# xmas_v4.net
KiCad netlist of a schematic drawn in EAGLE
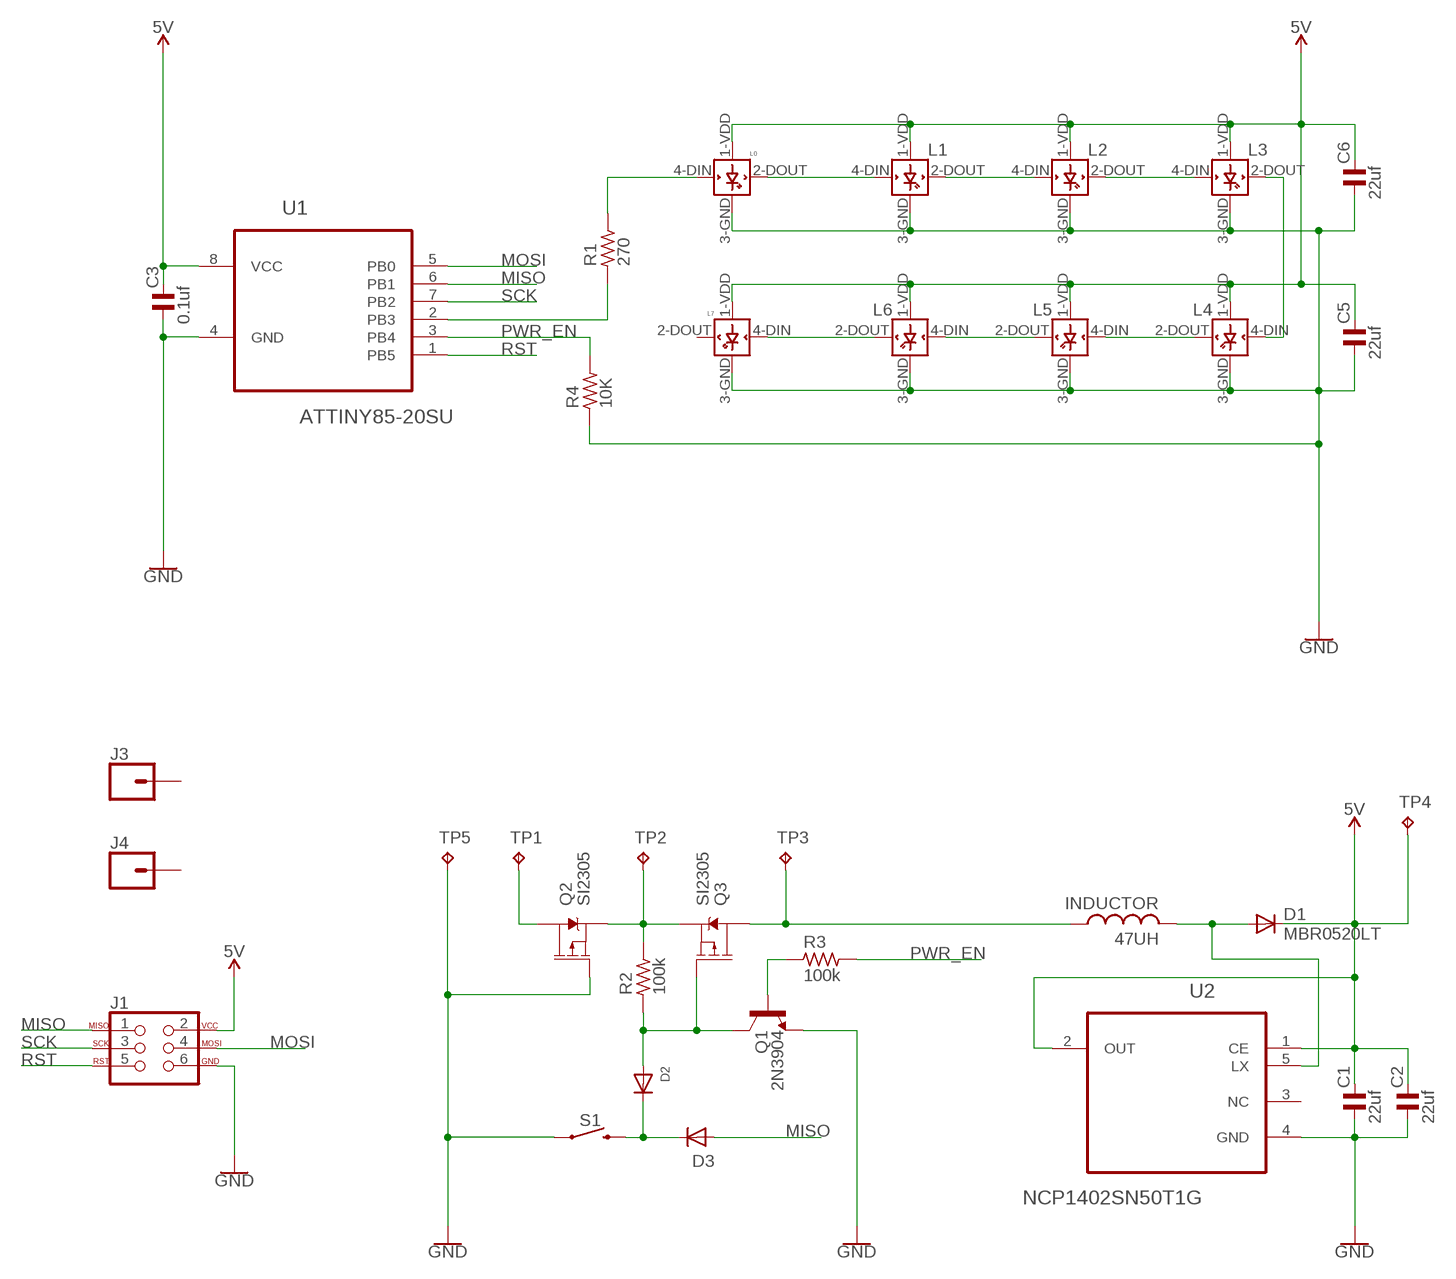
[diagram p0: schematic, sheet 1]

(export (version "E")
  (design (tool "Eeschema 10.0.6"))
  (components
    (comp (ref "47UH")
      (value "INDUCTOR")
      (footprint "eagle-import:CD32")
      (libsource (lib "eagle-import") (part "INDUCTOR"))
    )
    (comp (ref "C1")
      (value "22uf")
      (footprint "eagle-import:C0805MP")
      (libsource (lib "eagle-import") (part "C_0805MP"))
    )
    (comp (ref "C2")
      (value "22uf")
      (footprint "eagle-import:C0805MP")
      (libsource (lib "eagle-import") (part "C_0805MP"))
    )
    (comp (ref "C3")
      (value "0.1uf")
      (footprint "eagle-import:C0603MP")
      (libsource (lib "eagle-import") (part "C_0603MP"))
    )
    (comp (ref "C5")
      (value "22uf")
      (footprint "eagle-import:C0805MP")
      (libsource (lib "eagle-import") (part "C_0805MP"))
    )
    (comp (ref "C6")
      (value "22uf")
      (footprint "eagle-import:C0805MP")
      (libsource (lib "eagle-import") (part "C_0805MP"))
    )
    (comp (ref "D1")
      (value "MBR0520LT")
      (footprint "eagle-import:SOD123")
      (libsource (lib "eagle-import") (part "MBR0520LT"))
    )
    (comp (ref "D2")
      (value "DIODESOD-123")
      (footprint "eagle-import:SOD-123")
      (libsource (lib "eagle-import") (part "DIODESOD-123"))
    )
    (comp (ref "D3")
      (value "DIODESOD-123")
      (footprint "eagle-import:SOD-123")
      (libsource (lib "eagle-import") (part "DIODESOD-123"))
    )
    (comp (ref "J1")
      (value "AVR_SPI_PROG_3X2TESTPOINTS")
      (footprint "eagle-import:2X3_TEST_POINTS")
      (libsource (lib "eagle-import") (part "AVR_SPI_PROG_3X2TESTPOINTS"))
    )
    (comp (ref "J3")
      (value "CONN_01PTH_NO_SILK_KIT")
      (footprint "eagle-import:1X01NS_KIT")
      (libsource (lib "eagle-import") (part "CONN_01PTH_NO_SILK_KIT"))
    )
    (comp (ref "J4")
      (value "CONN_01PTH_NO_SILK_KIT")
      (footprint "eagle-import:1X01NS_KIT")
      (libsource (lib "eagle-import") (part "CONN_01PTH_NO_SILK_KIT"))
    )
    (comp (ref "L0")
      (value "WS2812B")
      (footprint "eagle-import:WS2812B")
      (libsource (lib "eagle-import") (part "WS2812B"))
    )
    (comp (ref "L1")
      (value "WS2812B")
      (footprint "eagle-import:WS2812B")
      (libsource (lib "eagle-import") (part "WS2812B"))
    )
    (comp (ref "L2")
      (value "WS2812B")
      (footprint "eagle-import:WS2812B")
      (libsource (lib "eagle-import") (part "WS2812B"))
    )
    (comp (ref "L3")
      (value "WS2812B")
      (footprint "eagle-import:WS2812B")
      (libsource (lib "eagle-import") (part "WS2812B"))
    )
    (comp (ref "L4")
      (value "WS2812B")
      (footprint "eagle-import:WS2812B")
      (libsource (lib "eagle-import") (part "WS2812B"))
    )
    (comp (ref "L5")
      (value "WS2812B")
      (footprint "eagle-import:WS2812B")
      (libsource (lib "eagle-import") (part "WS2812B"))
    )
    (comp (ref "L6")
      (value "WS2812B")
      (footprint "eagle-import:WS2812B")
      (libsource (lib "eagle-import") (part "WS2812B"))
    )
    (comp (ref "L7")
      (value "WS2812B")
      (footprint "eagle-import:WS2812B")
      (libsource (lib "eagle-import") (part "WS2812B"))
    )
    (comp (ref "Q1")
      (value "2N3904")
      (footprint "eagle-import:SOT23-3")
      (libsource (lib "eagle-import") (part "TRANS_NPN-MMBT2222AL"))
    )
    (comp (ref "Q2")
      (value "SI2305")
      (footprint "eagle-import:SOT23-3")
      (libsource (lib "eagle-import") (part "MOSFET_PCH-SI2309DS"))
    )
    (comp (ref "Q3")
      (value "SI2305")
      (footprint "eagle-import:SOT23-3")
      (libsource (lib "eagle-import") (part "MOSFET_PCH-SI2309DS"))
    )
    (comp (ref "R1")
      (value "270")
      (footprint "eagle-import:R0603MP")
      (libsource (lib "eagle-import") (part "R_0603MP"))
    )
    (comp (ref "R2")
      (value "100k")
      (footprint "eagle-import:R0603MP")
      (libsource (lib "eagle-import") (part "R_0603MP"))
    )
    (comp (ref "R3")
      (value "100k")
      (footprint "eagle-import:R0603MP")
      (libsource (lib "eagle-import") (part "R_0603MP"))
    )
    (comp (ref "R4")
      (value "10K")
      (footprint "eagle-import:R0805MP")
      (libsource (lib "eagle-import") (part "R_0805MP"))
    )
    (comp (ref "S1")
      (value "MOMENTARY-SWITCH-SPST-SMD-6.2MM-TALL")
      (footprint "eagle-import:TACTILE_SWITCH_SMD_6.2MM_TALL")
      (libsource (lib "eagle-import") (part "MOMENTARY-SWITCH-SPST-SMD-6.2MM-TALL"))
    )
    (comp (ref "TP1")
      (value "TPB1,27")
      (footprint "eagle-import:B1,27")
      (libsource (lib "eagle-import") (part "TPB1,27"))
    )
    (comp (ref "TP2")
      (value "TPB1,27")
      (footprint "eagle-import:B1,27")
      (libsource (lib "eagle-import") (part "TPB1,27"))
    )
    (comp (ref "TP3")
      (value "TPB1,27")
      (footprint "eagle-import:B1,27")
      (libsource (lib "eagle-import") (part "TPB1,27"))
    )
    (comp (ref "TP4")
      (value "TPB1,27")
      (footprint "eagle-import:B1,27")
      (libsource (lib "eagle-import") (part "TPB1,27"))
    )
    (comp (ref "TP5")
      (value "TPB1,27")
      (footprint "eagle-import:B1,27")
      (libsource (lib "eagle-import") (part "TPB1,27"))
    )
    (comp (ref "U1")
      (value "ATTINY85-20SU")
      (footprint "eagle-import:SOIC127P798X216-8N")
      (libsource (lib "eagle-import") (part "ATTINY85-20SU"))
    )
    (comp (ref "U2")
      (value "NCP1402SN50T1G")
      (footprint "eagle-import:SOT95P275X110-5N")
      (libsource (lib "eagle-import") (part "NCP1402SN50T1G"))
    )
  )
  (nets
    (net (code "1") (name "/MISO") (class "Default")
      (node (ref "D3") (pin "A") (pinfunction "A_A") (pintype "passive"))
      (node (ref "J1") (pin "1") (pinfunction "1_1") (pintype "passive"))
      (node (ref "U1") (pin "6") (pinfunction "PB1_6") (pintype "bidirectional"))
    )
    (net (code "2") (name "/MOSI") (class "Default")
      (node (ref "J1") (pin "4") (pinfunction "4_4") (pintype "passive"))
      (node (ref "U1") (pin "5") (pinfunction "PB0_5") (pintype "bidirectional"))
    )
    (net (code "3") (name "/PWR_EN") (class "Default")
      (node (ref "R3") (pin "2") (pinfunction "2_2") (pintype "passive"))
      (node (ref "R4") (pin "2") (pinfunction "2_2") (pintype "passive"))
      (node (ref "U1") (pin "3") (pinfunction "PB4_3") (pintype "bidirectional"))
    )
    (net (code "4") (name "/RST") (class "Default")
      (node (ref "J1") (pin "5") (pinfunction "5_5") (pintype "passive"))
      (node (ref "U1") (pin "1") (pinfunction "PB5_1") (pintype "bidirectional"))
    )
    (net (code "5") (name "/SCK") (class "Default")
      (node (ref "J1") (pin "3") (pinfunction "3_3") (pintype "passive"))
      (node (ref "U1") (pin "7") (pinfunction "PB2_7") (pintype "bidirectional"))
    )
    (net (code "6") (name "5V") (class "Default")
      (node (ref "C1") (pin "2") (pinfunction "2_2") (pintype "passive"))
      (node (ref "C2") (pin "2") (pinfunction "2_2") (pintype "passive"))
      (node (ref "C3") (pin "2") (pinfunction "2_2") (pintype "passive"))
      (node (ref "C5") (pin "2") (pinfunction "2_2") (pintype "passive"))
      (node (ref "C6") (pin "2") (pinfunction "2_2") (pintype "passive"))
      (node (ref "D1") (pin "C") (pinfunction "C_C") (pintype "passive"))
      (node (ref "J1") (pin "2") (pinfunction "2_2") (pintype "passive"))
      (node (ref "L0") (pin "1-VDD") (pinfunction "VDD_1-VDD") (pintype "bidirectional"))
      (node (ref "L1") (pin "1-VDD") (pinfunction "VDD_1-VDD") (pintype "bidirectional"))
      (node (ref "L2") (pin "1-VDD") (pinfunction "VDD_1-VDD") (pintype "bidirectional"))
      (node (ref "L3") (pin "1-VDD") (pinfunction "VDD_1-VDD") (pintype "bidirectional"))
      (node (ref "L4") (pin "1-VDD") (pinfunction "VDD_1-VDD") (pintype "bidirectional"))
      (node (ref "L5") (pin "1-VDD") (pinfunction "VDD_1-VDD") (pintype "bidirectional"))
      (node (ref "L6") (pin "1-VDD") (pinfunction "VDD_1-VDD") (pintype "bidirectional"))
      (node (ref "L7") (pin "1-VDD") (pinfunction "VDD_1-VDD") (pintype "bidirectional"))
      (node (ref "TP4") (pin "TP") (pinfunction "TP_TP") (pintype "input"))
      (node (ref "U1") (pin "8") (pinfunction "VCC_8") (pintype "power_in"))
      (node (ref "U2") (pin "1") (pinfunction "CE_1") (pintype "input"))
      (node (ref "U2") (pin "2") (pinfunction "OUT_2") (pintype "output"))
    )
    (net (code "7") (name "GND") (class "Default")
      (node (ref "C1") (pin "1") (pinfunction "1_1") (pintype "passive"))
      (node (ref "C2") (pin "1") (pinfunction "1_1") (pintype "passive"))
      (node (ref "C3") (pin "1") (pinfunction "1_1") (pintype "passive"))
      (node (ref "C5") (pin "1") (pinfunction "1_1") (pintype "passive"))
      (node (ref "C6") (pin "1") (pinfunction "1_1") (pintype "passive"))
      (node (ref "J1") (pin "6") (pinfunction "6_6") (pintype "passive"))
      (node (ref "L0") (pin "3-GND") (pinfunction "GND_3-GND") (pintype "bidirectional"))
      (node (ref "L1") (pin "3-GND") (pinfunction "GND_3-GND") (pintype "bidirectional"))
      (node (ref "L2") (pin "3-GND") (pinfunction "GND_3-GND") (pintype "bidirectional"))
      (node (ref "L3") (pin "3-GND") (pinfunction "GND_3-GND") (pintype "bidirectional"))
      (node (ref "L4") (pin "3-GND") (pinfunction "GND_3-GND") (pintype "bidirectional"))
      (node (ref "L5") (pin "3-GND") (pinfunction "GND_3-GND") (pintype "bidirectional"))
      (node (ref "L6") (pin "3-GND") (pinfunction "GND_3-GND") (pintype "bidirectional"))
      (node (ref "L7") (pin "3-GND") (pinfunction "GND_3-GND") (pintype "bidirectional"))
      (node (ref "Q1") (pin "2") (pinfunction "E_2") (pintype "passive"))
      (node (ref "Q2") (pin "1") (pinfunction "G_1") (pintype "bidirectional"))
      (node (ref "R4") (pin "1") (pinfunction "1_1") (pintype "passive"))
      (node (ref "S1") (pin "A2") (pinfunction "1_A2") (pintype "passive"))
      (node (ref "TP5") (pin "TP") (pinfunction "TP_TP") (pintype "input"))
      (node (ref "U1") (pin "4") (pinfunction "GND_4") (pintype "passive"))
      (node (ref "U2") (pin "4") (pinfunction "GND_4") (pintype "passive"))
    )
    (net (code "8") (name "Net-(L0-DIN)") (class "Default")
      (node (ref "L0") (pin "4-DIN") (pinfunction "DIN_4-DIN") (pintype "input"))
      (node (ref "R1") (pin "2") (pinfunction "2_2") (pintype "passive"))
    )
    (net (code "9") (name "Net-(L0-DOUT)") (class "Default")
      (node (ref "L0") (pin "2-DOUT") (pinfunction "DOUT_2-DOUT") (pintype "output"))
      (node (ref "L1") (pin "4-DIN") (pinfunction "DIN_4-DIN") (pintype "input"))
    )
    (net (code "10") (name "Net-(L1-DOUT)") (class "Default")
      (node (ref "L1") (pin "2-DOUT") (pinfunction "DOUT_2-DOUT") (pintype "output"))
      (node (ref "L2") (pin "4-DIN") (pinfunction "DIN_4-DIN") (pintype "input"))
    )
    (net (code "11") (name "Net-(L2-DOUT)") (class "Default")
      (node (ref "L2") (pin "2-DOUT") (pinfunction "DOUT_2-DOUT") (pintype "output"))
      (node (ref "L3") (pin "4-DIN") (pinfunction "DIN_4-DIN") (pintype "input"))
    )
    (net (code "12") (name "Net-(L3-DOUT)") (class "Default")
      (node (ref "L3") (pin "2-DOUT") (pinfunction "DOUT_2-DOUT") (pintype "output"))
      (node (ref "L4") (pin "4-DIN") (pinfunction "DIN_4-DIN") (pintype "input"))
    )
    (net (code "13") (name "Net-(L4-DOUT)") (class "Default")
      (node (ref "L4") (pin "2-DOUT") (pinfunction "DOUT_2-DOUT") (pintype "output"))
      (node (ref "L5") (pin "4-DIN") (pinfunction "DIN_4-DIN") (pintype "input"))
    )
    (net (code "14") (name "Net-(L5-DOUT)") (class "Default")
      (node (ref "L5") (pin "2-DOUT") (pinfunction "DOUT_2-DOUT") (pintype "output"))
      (node (ref "L6") (pin "4-DIN") (pinfunction "DIN_4-DIN") (pintype "input"))
    )
    (net (code "15") (name "Net-(L6-DOUT)") (class "Default")
      (node (ref "L6") (pin "2-DOUT") (pinfunction "DOUT_2-DOUT") (pintype "output"))
      (node (ref "L7") (pin "4-DIN") (pinfunction "DIN_4-DIN") (pintype "input"))
    )
    (net (code "16") (name "Net-(Q1-B)") (class "Default")
      (node (ref "Q1") (pin "1") (pinfunction "B_1") (pintype "passive"))
      (node (ref "R3") (pin "1") (pinfunction "1_1") (pintype "passive"))
    )
    (net (code "17") (name "Net-(Q1-C)") (class "Default")
      (node (ref "D2") (pin "A") (pinfunction "A_A") (pintype "passive"))
      (node (ref "Q1") (pin "3") (pinfunction "C_3") (pintype "passive"))
      (node (ref "Q3") (pin "1") (pinfunction "G_1") (pintype "bidirectional"))
      (node (ref "R2") (pin "1") (pinfunction "1_1") (pintype "passive"))
    )
    (net (code "18") (name "Net-(Q2-D)") (class "Default")
      (node (ref "Q2") (pin "3") (pinfunction "D_3") (pintype "bidirectional"))
      (node (ref "TP1") (pin "TP") (pinfunction "TP_TP") (pintype "input"))
    )
    (net (code "19") (name "Net-(Q2-S)") (class "Default")
      (node (ref "Q2") (pin "2") (pinfunction "S_2") (pintype "bidirectional"))
      (node (ref "Q3") (pin "2") (pinfunction "S_2") (pintype "bidirectional"))
      (node (ref "R2") (pin "2") (pinfunction "2_2") (pintype "passive"))
      (node (ref "TP2") (pin "TP") (pinfunction "TP_TP") (pintype "input"))
    )
    (net (code "20") (name "Net-(Q3-D)") (class "Default")
      (node (ref "47UH") (pin "1") (pinfunction "1_1") (pintype "passive"))
      (node (ref "Q3") (pin "3") (pinfunction "D_3") (pintype "bidirectional"))
      (node (ref "TP3") (pin "TP") (pinfunction "TP_TP") (pintype "input"))
    )
    (net (code "21") (name "Net-(S1-2)") (class "Default")
      (node (ref "D2") (pin "C") (pinfunction "C_C") (pintype "passive"))
      (node (ref "D3") (pin "C") (pinfunction "C_C") (pintype "passive"))
      (node (ref "S1") (pin "B2") (pinfunction "2_B2") (pintype "passive"))
    )
    (net (code "22") (name "Net-(U1-PB3)") (class "Default")
      (node (ref "R1") (pin "1") (pinfunction "1_1") (pintype "passive"))
      (node (ref "U1") (pin "2") (pinfunction "PB3_2") (pintype "bidirectional"))
    )
    (net (code "23") (name "Net-(U2-LX)") (class "Default")
      (node (ref "47UH") (pin "2") (pinfunction "2_2") (pintype "passive"))
      (node (ref "D1") (pin "A") (pinfunction "A_A") (pintype "passive"))
      (node (ref "U2") (pin "5") (pinfunction "LX_5") (pintype "input"))
    )
    (net (code "24") (name "unconnected-(J3-Pad1)") (class "Default")
      (node (ref "J3") (pin "1") (pinfunction "1_1") (pintype "passive"))
    )
    (net (code "25") (name "unconnected-(J4-Pad1)") (class "Default")
      (node (ref "J4") (pin "1") (pinfunction "1_1") (pintype "passive"))
    )
    (net (code "26") (name "unconnected-(L7-DOUT-Pad2-DOUT)") (class "Default")
      (node (ref "L7") (pin "2-DOUT") (pinfunction "DOUT_2-DOUT") (pintype "output"))
    )
    (net (code "27") (name "unconnected-(U2-NC-Pad3)") (class "Default")
      (node (ref "U2") (pin "3") (pinfunction "NC_3") (pintype "no_connect"))
    )
  )
)
